# FRONT-UNIT-3_2-WIDE.net
KiCad netlist of a schematic drawn in Altium Designer
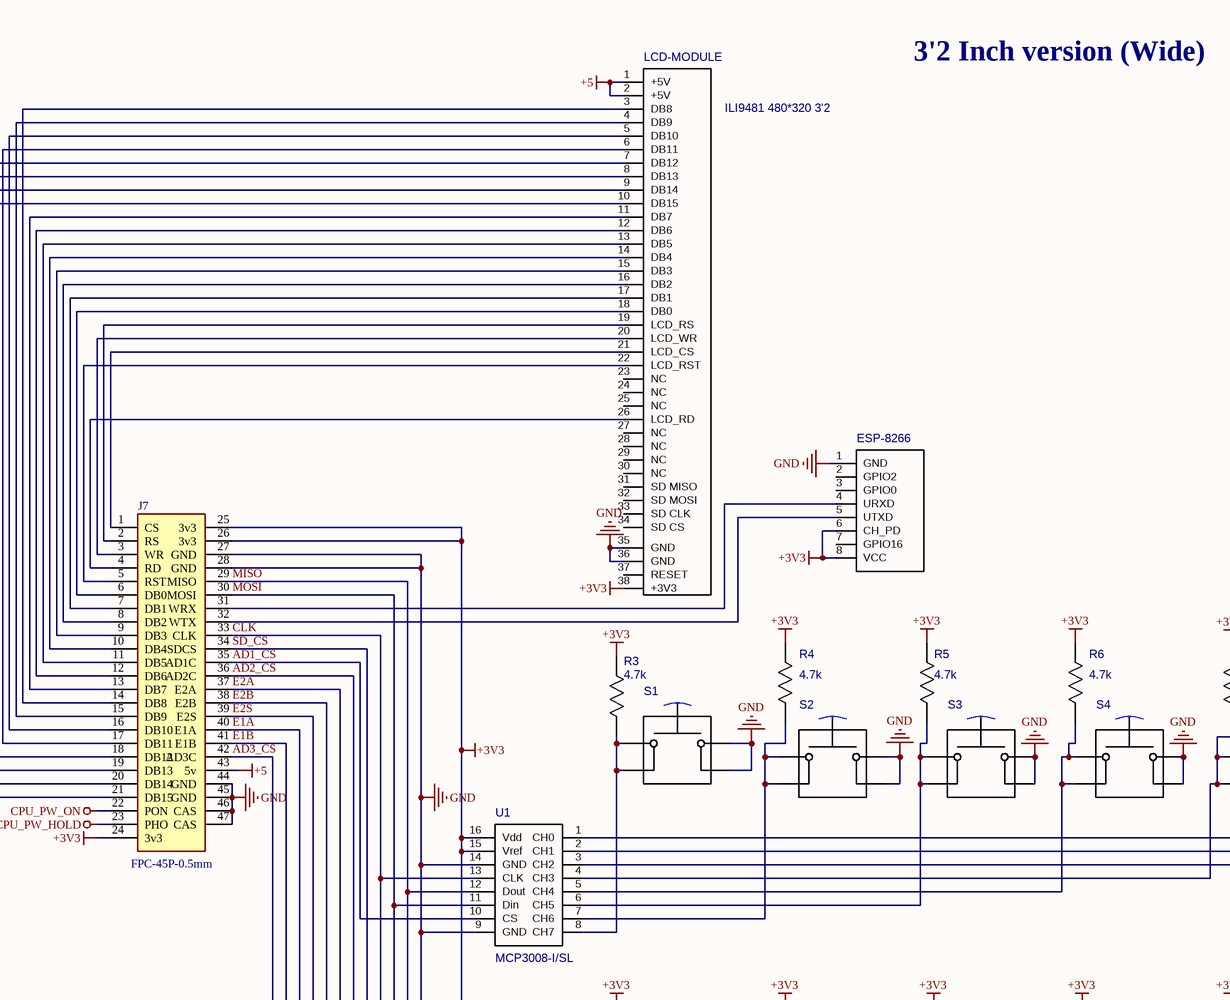
[diagram p0: FRONT-UNIT-3.2-WIDE.SCHDOC, top left]
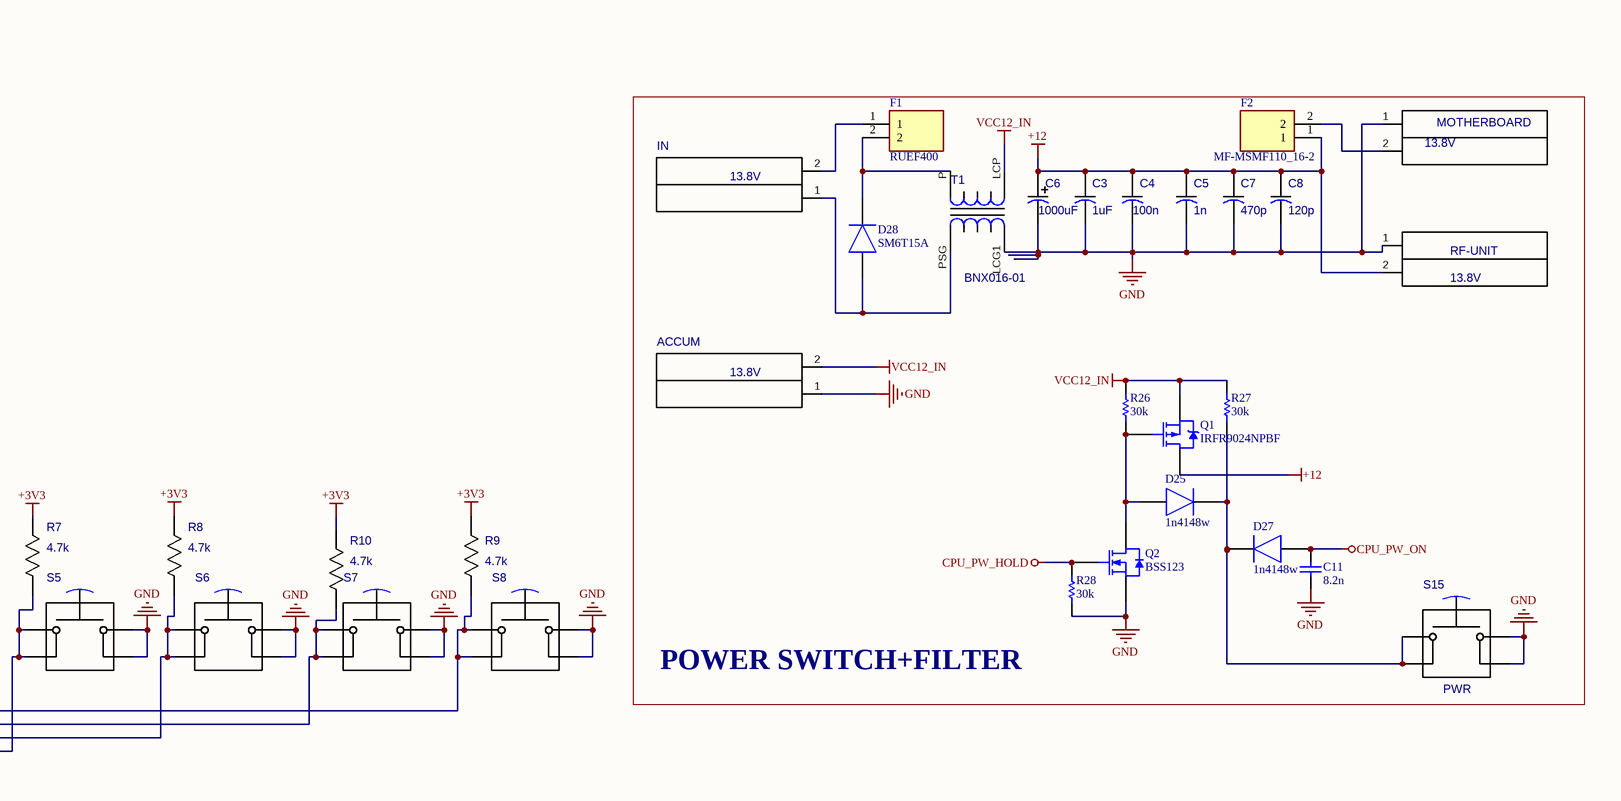
[diagram p1: FRONT-UNIT-3.2-WIDE.SCHDOC, top right]
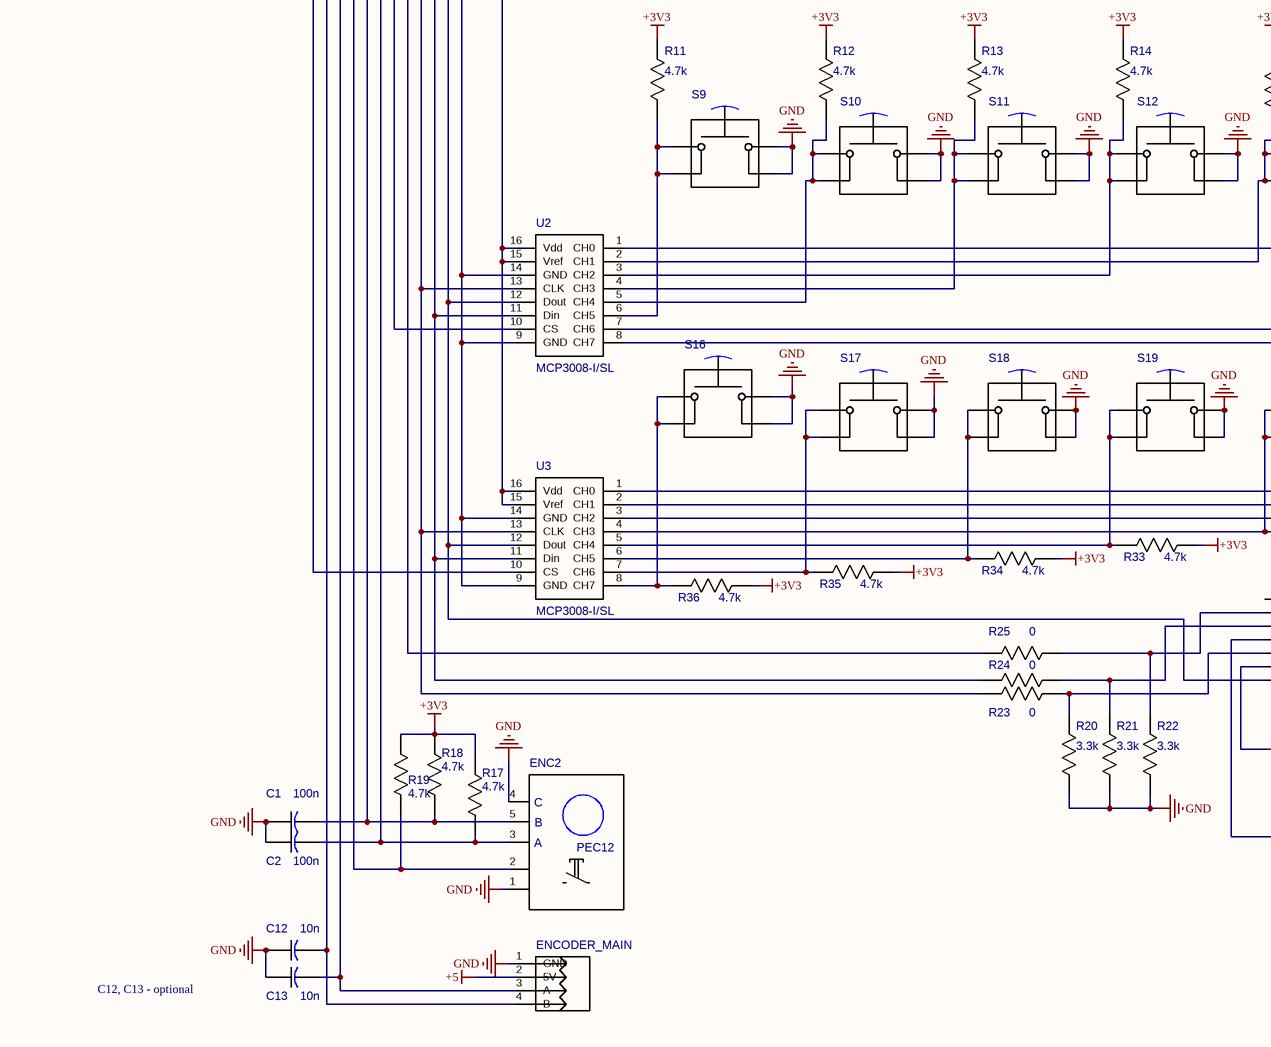
[diagram p2: FRONT-UNIT-3.2-WIDE.SCHDOC, bottom left]
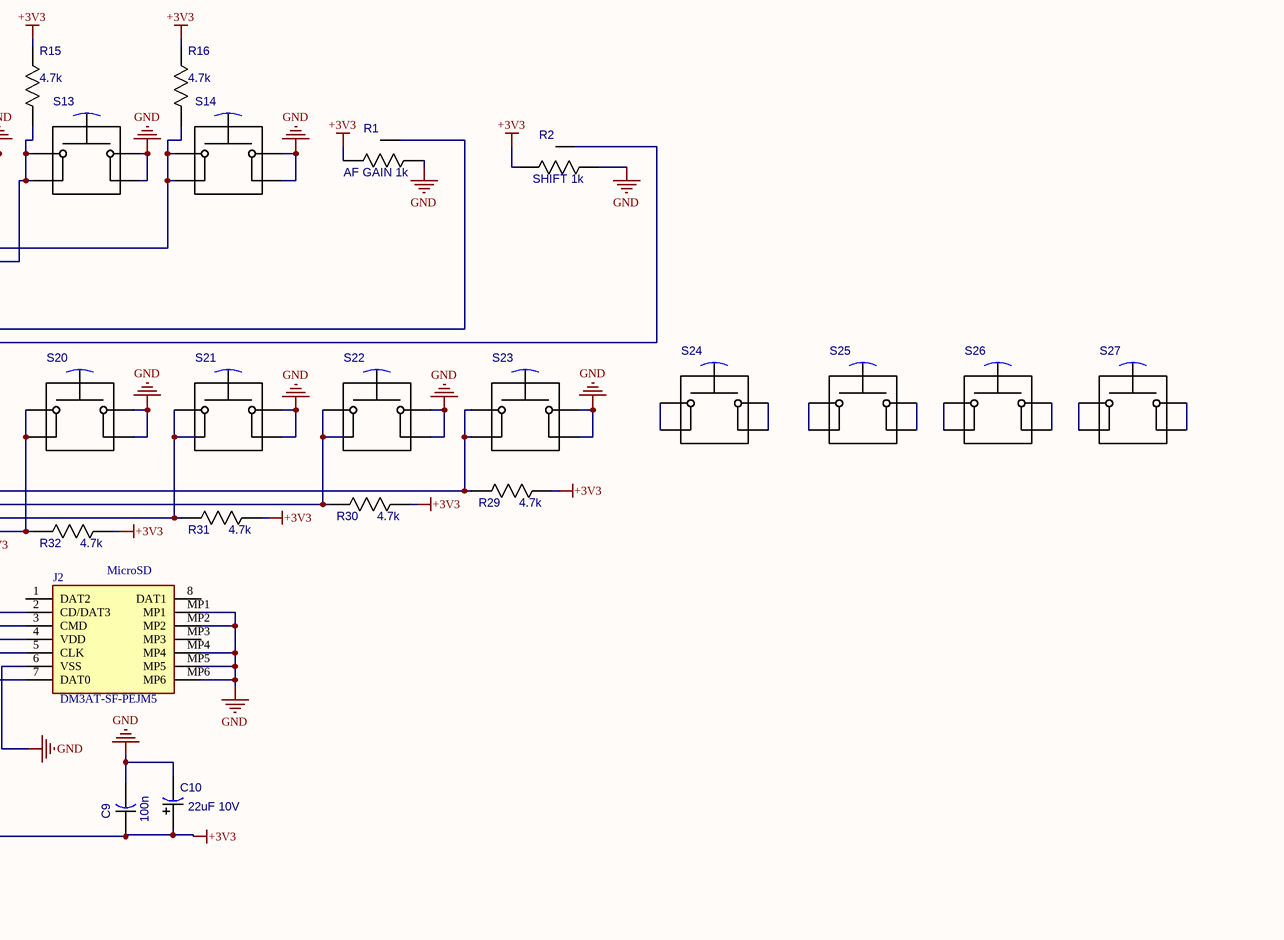
[diagram p3: FRONT-UNIT-3.2-WIDE.SCHDOC, bottom right]

(export (version "E")
  (design (tool "Eeschema 10.0.6"))
  (components
    (comp (ref "ACCUM")
      (value "13.8V")
      (footprint "JX2")
      (description "JX2")
      (libsource (lib "*") (part "JX2"))
    )
    (comp (ref "C1")
      (value "100n")
      (footprint "CAP_0805")
      (description "CAP_0805")
      (libsource (lib "*") (part "CAP_0805"))
    )
    (comp (ref "C2")
      (value "100n")
      (footprint "CAP_0805")
      (description "CAP_0805")
      (libsource (lib "*") (part "CAP_0805"))
    )
    (comp (ref "C3")
      (value "1uF")
      (footprint "CAP_1206")
      (description "CAP_1206")
      (libsource (lib "*") (part "CAP_1206"))
    )
    (comp (ref "C4")
      (value "100n")
      (footprint "CAP_1206")
      (description "CAP_1206")
      (libsource (lib "*") (part "CAP_1206"))
    )
    (comp (ref "C5")
      (value "1n")
      (footprint "CAP_1206")
      (description "CAP_1206")
      (libsource (lib "*") (part "CAP_1206"))
    )
    (comp (ref "C6")
      (value "1000uF")
      (footprint "CAP250RP")
      (description "CAP250RP")
      (libsource (lib "*") (part "CAP250RP"))
    )
    (comp (ref "C7")
      (value "470p")
      (footprint "CAP_1206")
      (description "CAP_1206")
      (libsource (lib "*") (part "CAP_1206"))
    )
    (comp (ref "C8")
      (value "120p")
      (footprint "CAP_1206")
      (description "CAP_1206")
      (libsource (lib "*") (part "CAP_1206"))
    )
    (comp (ref "C9")
      (value "100n")
      (footprint "CAP_0805")
      (description "CAP_0805")
      (libsource (lib "*") (part "CAP_0805"))
    )
    (comp (ref "C10")
      (value "22uF 10V")
      (footprint "EEEFC_sizeB")
      (description "EEEFC_sizeB")
      (libsource (lib "*") (part "EEEFC_sizeB"))
    )
    (comp (ref "C11")
      (value "8.2n")
      (footprint "CAPC2013X94X50LL20T25")
      (description "CAP_1206")
      (fields
        (field (name "MANUFACTURER") "AVX Interconnect / Elco")
        (field (name "PART NUMBER") "08055C822KAT2A")
      )
      (libsource (lib "Altium Content Vault") (part "CAP"))
    )
    (comp (ref "C12")
      (value "10n")
      (footprint "CAP_0805")
      (description "CAP_0805")
      (libsource (lib "*") (part "CAP_0805"))
    )
    (comp (ref "C13")
      (value "10n")
      (footprint "CAP_0805")
      (description "CAP_0805")
      (libsource (lib "*") (part "CAP_0805"))
    )
    (comp (ref "D25")
      (value "1n4148w")
      (footprint "SamacSys:SOD3716X135N")
      (description "Diode")
      (libsource (lib "*") (part "1n4148w"))
    )
    (comp (ref "D27")
      (value "1n4148w")
      (footprint "SamacSys:SOD3716X135N")
      (description "Diode")
      (libsource (lib "*") (part "1n4148w"))
    )
    (comp (ref "D28")
      (value "SM6T15A")
      (footprint "SamacSys:SMBJ36CATR")
      (description "Diode")
      (fields (field (name "MOUSER PART NUMBER") "511-SM6T15A") (field (name "RS PART NUMBER") "4864915P"))
      (libsource (lib "*") (part "SM6T15A"))
    )
    (comp (ref "ENC2") (value "PEC12") (footprint "PEC12") (libsource (lib "*") (part "PEC12")))
    (comp (ref "ENCODER_MAIN")
      (value "OPTICAL ENCODER")
      (footprint "644456-4")
      (libsource (lib "*") (part "644456-4"))
    )
    (comp (ref "ESP-8266")
      (value "ESP-01 ESP8266")
      (footprint "ESP-01 ESP8266")
      (libsource (lib "*") (part "ESP-01 ESP8266"))
    )
    (comp (ref "F1")
      (value "RUEF400")
      (footprint "SamacSys:RUEF400")
      (description "Fuse")
      (fields (field (name "MOUSER PART NUMBER") "650-RUEF400") (field (name "RS PART NUMBER") "5176837P"))
      (libsource (lib "*") (part "RUEF400"))
    )
    (comp (ref "F2")
      (value "MF-MSMF110_16-2")
      (footprint "SamacSys:FUSC4632X85N")
      (description "Fuse")
      (fields
        (field (name "MANUFACTURER_PART_NUMBER") "MF-MSMF110/16-2")
        (field (name "MOUSER PART NUMBER") "652-MF-MSMF110/16-2")
      )
      (libsource (lib "*") (part "MF-MSMF110_16-2"))
    )
    (comp (ref "IN") (value "13.8V") (footprint "JX2") (description "JX2") (libsource (lib "*") (part "JX2")))
    (comp (ref "J2")
      (value "DM3AT-SF-PEJM5")
      (footprint "SamacSys:DM3ATSFPEJM5")
      (description "Connector")
      (libsource (lib "*") (part "DM3AT-SF-PEJM5"))
    )
    (comp (ref "J7")
      (value "FPC-45P-0.5mm")
      (footprint "FRONT-UNIT-WIDE:FH12S45S05SH60")
      (description "Connector")
      (fields
        (field (name "MANUFACTURER_PART_NUMBER") "FH12S-45S-0.5SH(55)")
        (field (name "MOUSER PART NUMBER") "798-FH12S-45S-05SH55")
      )
      (libsource (lib "*") (part "FH12S-45S-0.5SH_55_"))
    )
    (comp (ref "LCD-MODULE")
      (value "ILI9481 480*320 3'2")
      (footprint "LCD-MODULE-3.2-480-320")
      (description "LCD-MODULE_3'2_480х320")
      (libsource (lib "FRONT-UNIT") (part "LCD-MODULE_3'2_480х320"))
    )
    (comp (ref "MOTHERBOARD")
      (value "13.8V")
      (footprint "JX2")
      (description "JX2")
      (libsource (lib "*") (part "JX2"))
    )
    (comp (ref "Q1")
      (value "IRFR9024NPBF")
      (footprint "ONSC-DPAK-3-369C-01_V")
      (description "IRFR9024NPBF, Транзистор, Р-канал 55В 11А")
      (fields (field (name "MANUFACTURER") "On Semiconductor") (field (name "PARTNUMBER") "NTD2955G"))
      (libsource (lib "Altium Content Vault") (part "ONSC-PMOS-G1S3D4-3_B"))
    )
    (comp (ref "Q2")
      (value "BSS123")
      (footprint "FAIR-SOT23-3_V")
      (fields (field (name "MANUFACTURER") "Fairchild"))
      (libsource (lib "Altium Content Vault") (part "NEMOS-GSD-3"))
    )
    (comp (ref "R1")
      (value "AF GAIN 1k")
      (footprint "PTV09")
      (description "Adjustable Resistor PTV09")
      (fields (field (name "Comment") "ptv09a-4225f-b102"))
      (libsource (lib "*") (part "PTV09"))
    )
    (comp (ref "R2")
      (value "SHIFT 1k")
      (footprint "PTV09")
      (description "Adjustable Resistor PTV09")
      (fields (field (name "Comment") "ptv09a-4225f-b102"))
      (libsource (lib "*") (part "PTV09"))
    )
    (comp (ref "R3")
      (value "4.7k")
      (footprint "RES_0805")
      (description "RES_0805")
      (libsource (lib "*") (part "RES_0805"))
    )
    (comp (ref "R4")
      (value "4.7k")
      (footprint "RES_0805")
      (description "RES_0805")
      (libsource (lib "*") (part "RES_0805"))
    )
    (comp (ref "R5")
      (value "4.7k")
      (footprint "RES_0805")
      (description "RES_0805")
      (libsource (lib "*") (part "RES_0805"))
    )
    (comp (ref "R6")
      (value "4.7k")
      (footprint "RES_0805")
      (description "RES_0805")
      (libsource (lib "*") (part "RES_0805"))
    )
    (comp (ref "R7")
      (value "4.7k")
      (footprint "RES_0805")
      (description "RES_0805")
      (libsource (lib "*") (part "RES_0805"))
    )
    (comp (ref "R8")
      (value "4.7k")
      (footprint "RES_0805")
      (description "RES_0805")
      (libsource (lib "*") (part "RES_0805"))
    )
    (comp (ref "R9")
      (value "4.7k")
      (footprint "RES_0805")
      (description "RES_0805")
      (libsource (lib "*") (part "RES_0805"))
    )
    (comp (ref "R10")
      (value "4.7k")
      (footprint "RES_0805")
      (description "RES_0805")
      (libsource (lib "*") (part "RES_0805"))
    )
    (comp (ref "R11")
      (value "4.7k")
      (footprint "RES_0805")
      (description "RES_0805")
      (libsource (lib "*") (part "RES_0805"))
    )
    (comp (ref "R12")
      (value "4.7k")
      (footprint "RES_0805")
      (description "RES_0805")
      (libsource (lib "*") (part "RES_0805"))
    )
    (comp (ref "R13")
      (value "4.7k")
      (footprint "RES_0805")
      (description "RES_0805")
      (libsource (lib "*") (part "RES_0805"))
    )
    (comp (ref "R14")
      (value "4.7k")
      (footprint "RES_0805")
      (description "RES_0805")
      (libsource (lib "*") (part "RES_0805"))
    )
    (comp (ref "R15")
      (value "4.7k")
      (footprint "RES_0805")
      (description "RES_0805")
      (libsource (lib "*") (part "RES_0805"))
    )
    (comp (ref "R16")
      (value "4.7k")
      (footprint "RES_0805")
      (description "RES_0805")
      (libsource (lib "*") (part "RES_0805"))
    )
    (comp (ref "R17")
      (value "4.7k")
      (footprint "RES_0805")
      (description "RES_0805")
      (libsource (lib "*") (part "RES_0805"))
    )
    (comp (ref "R18")
      (value "4.7k")
      (footprint "RES_0805")
      (description "RES_0805")
      (libsource (lib "*") (part "RES_0805"))
    )
    (comp (ref "R19")
      (value "4.7k")
      (footprint "RES_0805")
      (description "RES_0805")
      (libsource (lib "*") (part "RES_0805"))
    )
    (comp (ref "R20")
      (value "3.3k")
      (footprint "RES_0805")
      (description "RES_0805")
      (libsource (lib "*") (part "RES_0805"))
    )
    (comp (ref "R21")
      (value "3.3k")
      (footprint "RES_0805")
      (description "RES_0805")
      (libsource (lib "*") (part "RES_0805"))
    )
    (comp (ref "R22")
      (value "3.3k")
      (footprint "RES_0805")
      (description "RES_0805")
      (libsource (lib "*") (part "RES_0805"))
    )
    (comp (ref "R23")
      (value "0")
      (footprint "RES_0805")
      (description "RES_0805")
      (libsource (lib "*") (part "RES_0805"))
    )
    (comp (ref "R24")
      (value "0")
      (footprint "RES_0805")
      (description "RES_0805")
      (libsource (lib "*") (part "RES_0805"))
    )
    (comp (ref "R25")
      (value "0")
      (footprint "RES_0805")
      (description "RES_0805")
      (libsource (lib "*") (part "RES_0805"))
    )
    (comp (ref "R26")
      (value "30k")
      (footprint "RESC2013X60X40NL20T25")
      (description "RES_0805")
      (fields (field (name "MANUFACTURER") "Panasonic") (field (name "PART NUMBER") "ERA-6AEB303V"))
      (libsource (lib "Altium Content Vault") (part "RES"))
    )
    (comp (ref "R27")
      (value "30k")
      (footprint "RESC2013X60X40NL20T25")
      (description "RES_0805")
      (fields (field (name "MANUFACTURER") "Panasonic") (field (name "PART NUMBER") "ERA-6AEB303V"))
      (libsource (lib "Altium Content Vault") (part "RES"))
    )
    (comp (ref "R28")
      (value "30k")
      (footprint "RESC2013X60X40NL20T25")
      (description "RES_0805")
      (fields (field (name "MANUFACTURER") "Panasonic") (field (name "PART NUMBER") "ERA-6AEB303V"))
      (libsource (lib "Altium Content Vault") (part "RES"))
    )
    (comp (ref "R29")
      (value "4.7k")
      (footprint "RES_0805")
      (description "RES_0805")
      (libsource (lib "*") (part "RES_0805"))
    )
    (comp (ref "R30")
      (value "4.7k")
      (footprint "RES_0805")
      (description "RES_0805")
      (libsource (lib "*") (part "RES_0805"))
    )
    (comp (ref "R31")
      (value "4.7k")
      (footprint "RES_0805")
      (description "RES_0805")
      (libsource (lib "*") (part "RES_0805"))
    )
    (comp (ref "R32")
      (value "4.7k")
      (footprint "RES_0805")
      (description "RES_0805")
      (libsource (lib "*") (part "RES_0805"))
    )
    (comp (ref "R33")
      (value "4.7k")
      (footprint "RES_0805")
      (description "RES_0805")
      (libsource (lib "*") (part "RES_0805"))
    )
    (comp (ref "R34")
      (value "4.7k")
      (footprint "RES_0805")
      (description "RES_0805")
      (libsource (lib "*") (part "RES_0805"))
    )
    (comp (ref "R35")
      (value "4.7k")
      (footprint "RES_0805")
      (description "RES_0805")
      (libsource (lib "*") (part "RES_0805"))
    )
    (comp (ref "R36")
      (value "4.7k")
      (footprint "RES_0805")
      (description "RES_0805")
      (libsource (lib "*") (part "RES_0805"))
    )
    (comp (ref "RF-UNIT")
      (value "13.8V")
      (footprint "JX2")
      (description "JX2")
      (libsource (lib "*") (part "JX2"))
    )
    (comp (ref "S1")
      (value "PTS645SK50LFS")
      (footprint "PTS645SK50LFS")
      (fields (field (name "LCSC PART #") "test"))
      (libsource (lib "*") (part "PTS645SK50LFS"))
    )
    (comp (ref "S2")
      (value "PTS645SK50LFS")
      (footprint "PTS645SK50LFS")
      (libsource (lib "*") (part "PTS645SK50LFS"))
    )
    (comp (ref "S3")
      (value "PTS645SK50LFS")
      (footprint "PTS645SK50LFS")
      (libsource (lib "*") (part "PTS645SK50LFS"))
    )
    (comp (ref "S4")
      (value "PTS645SK50LFS")
      (footprint "PTS645SK50LFS")
      (libsource (lib "*") (part "PTS645SK50LFS"))
    )
    (comp (ref "S5")
      (value "PTS645SK50LFS")
      (footprint "PTS645SK50LFS")
      (libsource (lib "*") (part "PTS645SK50LFS"))
    )
    (comp (ref "S6")
      (value "PTS645SK50LFS")
      (footprint "PTS645SK50LFS")
      (libsource (lib "*") (part "PTS645SK50LFS"))
    )
    (comp (ref "S7")
      (value "PTS645SK50LFS")
      (footprint "PTS645SK50LFS")
      (libsource (lib "*") (part "PTS645SK50LFS"))
    )
    (comp (ref "S8")
      (value "PTS645SK50LFS")
      (footprint "PTS645SK50LFS")
      (libsource (lib "*") (part "PTS645SK50LFS"))
    )
    (comp (ref "S9")
      (value "PTS645SK50LFS")
      (footprint "PTS645SK50LFS")
      (libsource (lib "*") (part "PTS645SK50LFS"))
    )
    (comp (ref "S10")
      (value "PTS645SK50LFS")
      (footprint "PTS645SK50LFS")
      (libsource (lib "*") (part "PTS645SK50LFS"))
    )
    (comp (ref "S11")
      (value "PTS645SK50LFS")
      (footprint "PTS645SK50LFS")
      (libsource (lib "*") (part "PTS645SK50LFS"))
    )
    (comp (ref "S12")
      (value "PTS645SK50LFS")
      (footprint "PTS645SK50LFS")
      (libsource (lib "*") (part "PTS645SK50LFS"))
    )
    (comp (ref "S13")
      (value "PTS645SK50LFS")
      (footprint "PTS645SK50LFS")
      (libsource (lib "*") (part "PTS645SK50LFS"))
    )
    (comp (ref "S14")
      (value "PTS645SK50LFS")
      (footprint "PTS645SK50LFS")
      (libsource (lib "*") (part "PTS645SK50LFS"))
    )
    (comp (ref "S15")
      (value "PWR")
      (footprint "PTS645SK50LFS")
      (description "PTS645SK50LFS")
      (libsource (lib "*") (part "PTS645SK50LFS"))
    )
    (comp (ref "S16")
      (value "PTS645SK50LFS")
      (footprint "PTS645SK50LFS")
      (libsource (lib "*") (part "PTS645SK50LFS"))
    )
    (comp (ref "S17")
      (value "PTS645SK50LFS")
      (footprint "PTS645SK50LFS")
      (libsource (lib "*") (part "PTS645SK50LFS"))
    )
    (comp (ref "S18")
      (value "PTS645SK50LFS")
      (footprint "PTS645SK50LFS")
      (libsource (lib "*") (part "PTS645SK50LFS"))
    )
    (comp (ref "S19")
      (value "PTS645SK50LFS")
      (footprint "PTS645SK50LFS")
      (libsource (lib "*") (part "PTS645SK50LFS"))
    )
    (comp (ref "S20")
      (value "PTS645SK50LFS")
      (footprint "PTS645SK50LFS")
      (libsource (lib "*") (part "PTS645SK50LFS"))
    )
    (comp (ref "S21")
      (value "PTS645SK50LFS")
      (footprint "PTS645SK50LFS")
      (libsource (lib "*") (part "PTS645SK50LFS"))
    )
    (comp (ref "S22")
      (value "PTS645SK50LFS")
      (footprint "PTS645SK50LFS")
      (libsource (lib "*") (part "PTS645SK50LFS"))
    )
    (comp (ref "S23")
      (value "PTS645SK50LFS")
      (footprint "PTS645SK50LFS")
      (libsource (lib "*") (part "PTS645SK50LFS"))
    )
    (comp (ref "S24")
      (value "PTS645SK50LFS")
      (footprint "PTS645SK50LFS")
      (libsource (lib "*") (part "PTS645SK50LFS"))
    )
    (comp (ref "S25")
      (value "PTS645SK50LFS")
      (footprint "PTS645SK50LFS")
      (libsource (lib "*") (part "PTS645SK50LFS"))
    )
    (comp (ref "S26")
      (value "PTS645SK50LFS")
      (footprint "PTS645SK50LFS")
      (libsource (lib "*") (part "PTS645SK50LFS"))
    )
    (comp (ref "S27")
      (value "PTS645SK50LFS")
      (footprint "PTS645SK50LFS")
      (libsource (lib "*") (part "PTS645SK50LFS"))
    )
    (comp (ref "T1")
      (value "BNX016-01")
      (footprint "TRANSF_ICORE")
      (libsource (lib "*") (part "TRANSF_ICORE"))
    )
    (comp (ref "U1")
      (value "MCP3008-I/SL")
      (footprint "MCP3008-I/SL")
      (libsource (lib "*") (part "MCP3008-I/SL"))
    )
    (comp (ref "U2")
      (value "MCP3008-I/SL")
      (footprint "MCP3008-I/SL")
      (libsource (lib "*") (part "MCP3008-I/SL"))
    )
    (comp (ref "U3")
      (value "MCP3008-I/SL")
      (footprint "MCP3008-I/SL")
      (libsource (lib "*") (part "MCP3008-I/SL"))
    )
  )
  (nets
    (net (code "1") (name "+3V3") (class "Default")
      (node (ref "C10") (pin "1") (pinfunction "PLUS_1") (pintype "passive"))
      (node (ref "C9") (pin "1") (pinfunction "1_1") (pintype "passive"))
      (node (ref "ESP-8266") (pin "6") (pinfunction "CH_PD_6") (pintype "passive"))
      (node (ref "ESP-8266") (pin "8") (pinfunction "VCC_8") (pintype "passive"))
      (node (ref "J2") (pin "4") (pinfunction "VDD_4") (pintype "passive"))
      (node (ref "J7") (pin "24") (pinfunction "3v3_24") (pintype "passive"))
      (node (ref "J7") (pin "25") (pinfunction "3v3_25") (pintype "passive"))
      (node (ref "J7") (pin "26") (pinfunction "3v3_26") (pintype "passive"))
      (node (ref "LCD-MODULE") (pin "38") (pinfunction "+3V3_38") (pintype "passive"))
      (node (ref "R1") (pin "1") (pinfunction "CW_1") (pintype "passive"))
      (node (ref "R10") (pin "2") (pinfunction "2_2") (pintype "passive"))
      (node (ref "R11") (pin "2") (pinfunction "2_2") (pintype "passive"))
      (node (ref "R12") (pin "2") (pinfunction "2_2") (pintype "passive"))
      (node (ref "R13") (pin "2") (pinfunction "2_2") (pintype "passive"))
      (node (ref "R14") (pin "2") (pinfunction "2_2") (pintype "passive"))
      (node (ref "R15") (pin "2") (pinfunction "2_2") (pintype "passive"))
      (node (ref "R16") (pin "2") (pinfunction "2_2") (pintype "passive"))
      (node (ref "R17") (pin "2") (pinfunction "2_2") (pintype "passive"))
      (node (ref "R18") (pin "2") (pinfunction "2_2") (pintype "passive"))
      (node (ref "R19") (pin "2") (pinfunction "2_2") (pintype "passive"))
      (node (ref "R2") (pin "1") (pinfunction "CW_1") (pintype "passive"))
      (node (ref "R29") (pin "2") (pinfunction "2_2") (pintype "passive"))
      (node (ref "R3") (pin "2") (pinfunction "2_2") (pintype "passive"))
      (node (ref "R30") (pin "2") (pinfunction "2_2") (pintype "passive"))
      (node (ref "R31") (pin "2") (pinfunction "2_2") (pintype "passive"))
      (node (ref "R32") (pin "2") (pinfunction "2_2") (pintype "passive"))
      (node (ref "R33") (pin "2") (pinfunction "2_2") (pintype "passive"))
      (node (ref "R34") (pin "2") (pinfunction "2_2") (pintype "passive"))
      (node (ref "R35") (pin "2") (pinfunction "2_2") (pintype "passive"))
      (node (ref "R36") (pin "2") (pinfunction "2_2") (pintype "passive"))
      (node (ref "R4") (pin "2") (pinfunction "2_2") (pintype "passive"))
      (node (ref "R5") (pin "2") (pinfunction "2_2") (pintype "passive"))
      (node (ref "R6") (pin "2") (pinfunction "2_2") (pintype "passive"))
      (node (ref "R7") (pin "2") (pinfunction "2_2") (pintype "passive"))
      (node (ref "R8") (pin "2") (pinfunction "2_2") (pintype "passive"))
      (node (ref "R9") (pin "2") (pinfunction "2_2") (pintype "passive"))
      (node (ref "U1") (pin "15") (pinfunction "Vref_15") (pintype "passive"))
      (node (ref "U1") (pin "16") (pinfunction "Vdd_16") (pintype "passive"))
      (node (ref "U2") (pin "15") (pinfunction "Vref_15") (pintype "passive"))
      (node (ref "U2") (pin "16") (pinfunction "Vdd_16") (pintype "passive"))
      (node (ref "U3") (pin "15") (pinfunction "Vref_15") (pintype "passive"))
      (node (ref "U3") (pin "16") (pinfunction "Vdd_16") (pintype "passive"))
    )
    (net (code "2") (name "+5") (class "Default")
      (node (ref "ENCODER_MAIN") (pin "2") (pinfunction "5V_2") (pintype "passive"))
      (node (ref "J7") (pin "43") (pinfunction "5v_43") (pintype "passive"))
      (node (ref "LCD-MODULE") (pin "1") (pinfunction "+5V_1") (pintype "passive"))
      (node (ref "LCD-MODULE") (pin "2") (pinfunction "+5V_2") (pintype "passive"))
    )
    (net (code "3") (name "+12") (class "Default")
      (node (ref "C3") (pin "1") (pinfunction "1_1") (pintype "passive"))
      (node (ref "C4") (pin "1") (pinfunction "1_1") (pintype "passive"))
      (node (ref "C5") (pin "1") (pinfunction "1_1") (pintype "passive"))
      (node (ref "C6") (pin "1") (pinfunction "PLUS_1") (pintype "passive"))
      (node (ref "C7") (pin "1") (pinfunction "1_1") (pintype "passive"))
      (node (ref "C8") (pin "1") (pinfunction "1_1") (pintype "passive"))
      (node (ref "F2") (pin "1") (pinfunction "1_1") (pintype "passive"))
      (node (ref "Q1") (pin "4") (pinfunction "D_4") (pintype "passive"))
      (node (ref "RF-UNIT") (pin "2") (pinfunction "2_2") (pintype "passive"))
    )
    (net (code "4") (name "/AD1_CS") (class "Default")
      (node (ref "J7") (pin "35") (pinfunction "AD1C_35") (pintype "passive"))
      (node (ref "U1") (pin "10") (pinfunction "CS_10") (pintype "passive"))
    )
    (net (code "5") (name "/AD2_CS") (class "Default")
      (node (ref "J7") (pin "36") (pinfunction "AD2C_36") (pintype "passive"))
      (node (ref "U2") (pin "10") (pinfunction "CS_10") (pintype "passive"))
    )
    (net (code "6") (name "/AD3_CS") (class "Default")
      (node (ref "J7") (pin "42") (pinfunction "AD3C_42") (pintype "passive"))
      (node (ref "U3") (pin "10") (pinfunction "CS_10") (pintype "passive"))
    )
    (net (code "7") (name "/CLK") (class "Default")
      (node (ref "J7") (pin "33") (pinfunction "CLK_33") (pintype "passive"))
      (node (ref "R23") (pin "2") (pinfunction "2_2") (pintype "passive"))
      (node (ref "U1") (pin "13") (pinfunction "CLK_13") (pintype "passive"))
      (node (ref "U2") (pin "13") (pinfunction "CLK_13") (pintype "passive"))
      (node (ref "U3") (pin "13") (pinfunction "CLK_13") (pintype "passive"))
    )
    (net (code "8") (name "/E1A") (class "Default")
      (node (ref "C13") (pin "2") (pinfunction "2_2") (pintype "passive"))
      (node (ref "ENCODER_MAIN") (pin "3") (pinfunction "A_3") (pintype "passive"))
      (node (ref "J7") (pin "40") (pinfunction "E1A_40") (pintype "passive"))
    )
    (net (code "9") (name "/E1B") (class "Default")
      (node (ref "C12") (pin "2") (pinfunction "2_2") (pintype "passive"))
      (node (ref "ENCODER_MAIN") (pin "4") (pinfunction "B_4") (pintype "passive"))
      (node (ref "J7") (pin "41") (pinfunction "E1B_41") (pintype "passive"))
    )
    (net (code "10") (name "/E2A") (class "Default")
      (node (ref "C2") (pin "2") (pinfunction "2_2") (pintype "passive"))
      (node (ref "ENC2") (pin "3") (pinfunction "A_3") (pintype "passive"))
      (node (ref "J7") (pin "37") (pinfunction "E2A_37") (pintype "passive"))
      (node (ref "R17") (pin "1") (pinfunction "1_1") (pintype "passive"))
    )
    (net (code "11") (name "/E2B") (class "Default")
      (node (ref "C1") (pin "2") (pinfunction "2_2") (pintype "passive"))
      (node (ref "ENC2") (pin "5") (pinfunction "B_5") (pintype "passive"))
      (node (ref "J7") (pin "38") (pinfunction "E2B_38") (pintype "passive"))
      (node (ref "R18") (pin "1") (pinfunction "1_1") (pintype "passive"))
    )
    (net (code "12") (name "/E2S") (class "Default")
      (node (ref "ENC2") (pin "2") (pinfunction "2_2") (pintype "passive"))
      (node (ref "J7") (pin "39") (pinfunction "E2S_39") (pintype "passive"))
      (node (ref "R19") (pin "1") (pinfunction "1_1") (pintype "passive"))
    )
    (net (code "13") (name "/MISO") (class "Default")
      (node (ref "J2") (pin "7") (pinfunction "DAT0_7") (pintype "passive"))
      (node (ref "J7") (pin "29") (pinfunction "MISO_29") (pintype "passive"))
      (node (ref "U1") (pin "12") (pinfunction "Dout_12") (pintype "passive"))
      (node (ref "U2") (pin "12") (pinfunction "Dout_12") (pintype "passive"))
      (node (ref "U3") (pin "12") (pinfunction "Dout_12") (pintype "passive"))
    )
    (net (code "14") (name "/MOSI") (class "Default")
      (node (ref "J7") (pin "30") (pinfunction "MOSI_30") (pintype "passive"))
      (node (ref "R24") (pin "2") (pinfunction "2_2") (pintype "passive"))
      (node (ref "U1") (pin "11") (pinfunction "Din_11") (pintype "passive"))
      (node (ref "U2") (pin "11") (pinfunction "Din_11") (pintype "passive"))
      (node (ref "U3") (pin "11") (pinfunction "Din_11") (pintype "passive"))
    )
    (net (code "15") (name "/SD_CS") (class "Default")
      (node (ref "J7") (pin "34") (pinfunction "SDCS_34") (pintype "passive"))
      (node (ref "R25") (pin "2") (pinfunction "2_2") (pintype "passive"))
    )
    (net (code "16") (name "CPU_PW_HOLD") (class "Default")
      (node (ref "J7") (pin "23") (pinfunction "PHO_23") (pintype "passive"))
      (node (ref "Q2") (pin "1") (pinfunction "G_1") (pintype "passive"))
      (node (ref "R28") (pin "2") (pinfunction "2_2") (pintype "passive"))
    )
    (net (code "17") (name "CPU_PW_ON") (class "Default")
      (node (ref "C11") (pin "2") (pinfunction "2_2") (pintype "passive"))
      (node (ref "D27") (pin "2") (pinfunction "A_2") (pintype "passive"))
      (node (ref "J7") (pin "22") (pinfunction "PON_22") (pintype "passive"))
    )
    (net (code "18") (name "GND") (class "Default")
      (node (ref "ACCUM") (pin "1") (pinfunction "1_1") (pintype "passive"))
      (node (ref "C1") (pin "1") (pinfunction "1_1") (pintype "passive"))
      (node (ref "C10") (pin "2") (pinfunction "MINUS_2") (pintype "passive"))
      (node (ref "C11") (pin "1") (pinfunction "1_1") (pintype "passive"))
      (node (ref "C12") (pin "1") (pinfunction "1_1") (pintype "passive"))
      (node (ref "C13") (pin "1") (pinfunction "1_1") (pintype "passive"))
      (node (ref "C2") (pin "1") (pinfunction "1_1") (pintype "passive"))
      (node (ref "C3") (pin "2") (pinfunction "2_2") (pintype "passive"))
      (node (ref "C4") (pin "2") (pinfunction "2_2") (pintype "passive"))
      (node (ref "C5") (pin "2") (pinfunction "2_2") (pintype "passive"))
      (node (ref "C6") (pin "2") (pinfunction "MINUS_2") (pintype "passive"))
      (node (ref "C7") (pin "2") (pinfunction "2_2") (pintype "passive"))
      (node (ref "C8") (pin "2") (pinfunction "2_2") (pintype "passive"))
      (node (ref "C9") (pin "2") (pinfunction "2_2") (pintype "passive"))
      (node (ref "ENC2") (pin "1") (pinfunction "1_1") (pintype "passive"))
      (node (ref "ENC2") (pin "4") (pinfunction "C_4") (pintype "passive"))
      (node (ref "ENCODER_MAIN") (pin "1") (pinfunction "GND_1") (pintype "passive"))
      (node (ref "ESP-8266") (pin "1") (pinfunction "GND_1") (pintype "passive"))
      (node (ref "J2") (pin "6") (pinfunction "VSS_6") (pintype "passive"))
      (node (ref "J2") (pin "MP1") (pinfunction "MP1_MP1") (pintype "passive"))
      (node (ref "J2") (pin "MP2") (pinfunction "MP2_MP2") (pintype "passive"))
      (node (ref "J2") (pin "MP4") (pinfunction "MP4_MP4") (pintype "passive"))
      (node (ref "J2") (pin "MP5") (pinfunction "MP5_MP5") (pintype "passive"))
      (node (ref "J2") (pin "MP6") (pinfunction "MP6_MP6") (pintype "passive"))
      (node (ref "J7") (pin "27") (pinfunction "GND_27") (pintype "passive"))
      (node (ref "J7") (pin "28") (pinfunction "GND_28") (pintype "passive"))
      (node (ref "J7") (pin "44") (pinfunction "GND_44") (pintype "passive"))
      (node (ref "J7") (pin "45") (pinfunction "GND_45") (pintype "passive"))
      (node (ref "J7") (pin "46") (pinfunction "CAS_46") (pintype "passive"))
      (node (ref "J7") (pin "47") (pinfunction "CAS_47") (pintype "passive"))
      (node (ref "LCD-MODULE") (pin "35") (pinfunction "GND_35") (pintype "passive"))
      (node (ref "LCD-MODULE") (pin "36") (pinfunction "GND_36") (pintype "passive"))
      (node (ref "MOTHERBOARD") (pin "1") (pinfunction "1_1") (pintype "passive"))
      (node (ref "Q2") (pin "2") (pinfunction "S_2") (pintype "passive"))
      (node (ref "R1") (pin "3") (pinfunction "CCW_3") (pintype "passive"))
      (node (ref "R2") (pin "3") (pinfunction "CCW_3") (pintype "passive"))
      (node (ref "R20") (pin "1") (pinfunction "1_1") (pintype "passive"))
      (node (ref "R21") (pin "1") (pinfunction "1_1") (pintype "passive"))
      (node (ref "R22") (pin "1") (pinfunction "1_1") (pintype "passive"))
      (node (ref "R28") (pin "1") (pinfunction "1_1") (pintype "passive"))
      (node (ref "RF-UNIT") (pin "1") (pinfunction "1_1") (pintype "passive"))
      (node (ref "S1") (pin "3") (pinfunction "B_3") (pintype "passive"))
      (node (ref "S1") (pin "4") (pinfunction "B_4") (pintype "passive"))
      (node (ref "S10") (pin "3") (pinfunction "B_3") (pintype "passive"))
      (node (ref "S10") (pin "4") (pinfunction "B_4") (pintype "passive"))
      (node (ref "S11") (pin "3") (pinfunction "B_3") (pintype "passive"))
      (node (ref "S11") (pin "4") (pinfunction "B_4") (pintype "passive"))
      (node (ref "S12") (pin "3") (pinfunction "B_3") (pintype "passive"))
      (node (ref "S12") (pin "4") (pinfunction "B_4") (pintype "passive"))
      (node (ref "S13") (pin "3") (pinfunction "B_3") (pintype "passive"))
      (node (ref "S13") (pin "4") (pinfunction "B_4") (pintype "passive"))
      (node (ref "S14") (pin "3") (pinfunction "B_3") (pintype "passive"))
      (node (ref "S14") (pin "4") (pinfunction "B_4") (pintype "passive"))
      (node (ref "S15") (pin "3") (pinfunction "B_3") (pintype "passive"))
      (node (ref "S15") (pin "4") (pinfunction "B_4") (pintype "passive"))
      (node (ref "S16") (pin "3") (pinfunction "B_3") (pintype "passive"))
      (node (ref "S16") (pin "4") (pinfunction "B_4") (pintype "passive"))
      (node (ref "S17") (pin "3") (pinfunction "B_3") (pintype "passive"))
      (node (ref "S17") (pin "4") (pinfunction "B_4") (pintype "passive"))
      (node (ref "S18") (pin "3") (pinfunction "B_3") (pintype "passive"))
      (node (ref "S18") (pin "4") (pinfunction "B_4") (pintype "passive"))
      (node (ref "S19") (pin "3") (pinfunction "B_3") (pintype "passive"))
      (node (ref "S19") (pin "4") (pinfunction "B_4") (pintype "passive"))
      (node (ref "S2") (pin "3") (pinfunction "B_3") (pintype "passive"))
      (node (ref "S2") (pin "4") (pinfunction "B_4") (pintype "passive"))
      (node (ref "S20") (pin "3") (pinfunction "B_3") (pintype "passive"))
      (node (ref "S20") (pin "4") (pinfunction "B_4") (pintype "passive"))
      (node (ref "S21") (pin "3") (pinfunction "B_3") (pintype "passive"))
      (node (ref "S21") (pin "4") (pinfunction "B_4") (pintype "passive"))
      (node (ref "S22") (pin "3") (pinfunction "B_3") (pintype "passive"))
      (node (ref "S22") (pin "4") (pinfunction "B_4") (pintype "passive"))
      (node (ref "S23") (pin "3") (pinfunction "B_3") (pintype "passive"))
      (node (ref "S23") (pin "4") (pinfunction "B_4") (pintype "passive"))
      (node (ref "S3") (pin "3") (pinfunction "B_3") (pintype "passive"))
      (node (ref "S3") (pin "4") (pinfunction "B_4") (pintype "passive"))
      (node (ref "S4") (pin "3") (pinfunction "B_3") (pintype "passive"))
      (node (ref "S4") (pin "4") (pinfunction "B_4") (pintype "passive"))
      (node (ref "S5") (pin "3") (pinfunction "B_3") (pintype "passive"))
      (node (ref "S5") (pin "4") (pinfunction "B_4") (pintype "passive"))
      (node (ref "S6") (pin "3") (pinfunction "B_3") (pintype "passive"))
      (node (ref "S6") (pin "4") (pinfunction "B_4") (pintype "passive"))
      (node (ref "S7") (pin "3") (pinfunction "B_3") (pintype "passive"))
      (node (ref "S7") (pin "4") (pinfunction "B_4") (pintype "passive"))
      (node (ref "S8") (pin "3") (pinfunction "B_3") (pintype "passive"))
      (node (ref "S8") (pin "4") (pinfunction "B_4") (pintype "passive"))
      (node (ref "S9") (pin "3") (pinfunction "B_3") (pintype "passive"))
      (node (ref "S9") (pin "4") (pinfunction "B_4") (pintype "passive"))
      (node (ref "T1") (pin "LCG1") (pinfunction "S2_LCG1") (pintype "passive"))
      (node (ref "T1") (pin "LCG2") (pinfunction "0_LCG2") (pintype "passive"))
      (node (ref "T1") (pin "LCG3") (pinfunction "0_LCG3") (pintype "passive"))
      (node (ref "U1") (pin "14") (pinfunction "GND_14") (pintype "passive"))
      (node (ref "U1") (pin "9") (pinfunction "GND_9") (pintype "passive"))
      (node (ref "U2") (pin "14") (pinfunction "GND_14") (pintype "passive"))
      (node (ref "U2") (pin "9") (pinfunction "GND_9") (pintype "passive"))
      (node (ref "U3") (pin "14") (pinfunction "GND_14") (pintype "passive"))
      (node (ref "U3") (pin "9") (pinfunction "GND_9") (pintype "passive"))
    )
    (net (code "19") (name "Net-(D25-A)") (class "Default")
      (node (ref "D25") (pin "2") (pinfunction "A_2") (pintype "passive"))
      (node (ref "Q1") (pin "1") (pinfunction "G_1") (pintype "passive"))
      (node (ref "Q2") (pin "3") (pinfunction "D_3") (pintype "passive"))
      (node (ref "R26") (pin "1") (pinfunction "1_1") (pintype "passive"))
    )
    (net (code "20") (name "Net-(D25-K)") (class "Default")
      (node (ref "D25") (pin "1") (pinfunction "K_1") (pintype "passive"))
      (node (ref "D27") (pin "1") (pinfunction "K_1") (pintype "passive"))
      (node (ref "R27") (pin "1") (pinfunction "1_1") (pintype "passive"))
      (node (ref "S15") (pin "1") (pinfunction "A_1") (pintype "passive"))
      (node (ref "S15") (pin "2") (pinfunction "A_2") (pintype "passive"))
    )
    (net (code "21") (name "Net-(D28-A)") (class "Default")
      (node (ref "D28") (pin "2") (pinfunction "A_2") (pintype "passive"))
      (node (ref "IN") (pin "1") (pinfunction "1_1") (pintype "passive"))
      (node (ref "T1") (pin "PSG") (pinfunction "S1_PSG") (pintype "passive"))
    )
    (net (code "22") (name "Net-(D28-K)") (class "Default")
      (node (ref "D28") (pin "1") (pinfunction "K_1") (pintype "passive"))
      (node (ref "F1") (pin "2") (pinfunction "2_2") (pintype "passive"))
      (node (ref "T1") (pin "P") (pinfunction "P1_P") (pintype "passive"))
    )
    (net (code "23") (name "Net-(ESP-8266-URXD)") (class "Default")
      (node (ref "ESP-8266") (pin "4") (pinfunction "URXD_4") (pintype "passive"))
      (node (ref "J7") (pin "31") (pinfunction "WRX_31") (pintype "passive"))
    )
    (net (code "24") (name "Net-(ESP-8266-UTXD)") (class "Default")
      (node (ref "ESP-8266") (pin "5") (pinfunction "UTXD_5") (pintype "passive"))
      (node (ref "J7") (pin "32") (pinfunction "WTX_32") (pintype "passive"))
    )
    (net (code "25") (name "Net-(F1-Pad1)") (class "Default")
      (node (ref "F1") (pin "1") (pinfunction "1_1") (pintype "passive"))
      (node (ref "IN") (pin "2") (pinfunction "2_2") (pintype "passive"))
    )
    (net (code "26") (name "Net-(F2-Pad2)") (class "Default")
      (node (ref "F2") (pin "2") (pinfunction "2_2") (pintype "passive"))
      (node (ref "MOTHERBOARD") (pin "2") (pinfunction "2_2") (pintype "passive"))
    )
    (net (code "27") (name "Net-(J2-CD{slash}DAT3)") (class "Default")
      (node (ref "J2") (pin "2") (pinfunction "CD/DAT3_2") (pintype "passive"))
      (node (ref "R22") (pin "2") (pinfunction "2_2") (pintype "passive"))
      (node (ref "R25") (pin "1") (pinfunction "1_1") (pintype "passive"))
    )
    (net (code "28") (name "Net-(J2-CLK)") (class "Default")
      (node (ref "J2") (pin "5") (pinfunction "CLK_5") (pintype "passive"))
      (node (ref "R20") (pin "2") (pinfunction "2_2") (pintype "passive"))
      (node (ref "R23") (pin "1") (pinfunction "1_1") (pintype "passive"))
    )
    (net (code "29") (name "Net-(J2-CMD)") (class "Default")
      (node (ref "J2") (pin "3") (pinfunction "CMD_3") (pintype "passive"))
      (node (ref "R21") (pin "2") (pinfunction "2_2") (pintype "passive"))
      (node (ref "R24") (pin "1") (pinfunction "1_1") (pintype "passive"))
    )
    (net (code "30") (name "Net-(J7-CS)") (class "Default")
      (node (ref "J7") (pin "1") (pinfunction "CS_1") (pintype "passive"))
      (node (ref "LCD-MODULE") (pin "21") (pinfunction "LCD_CS_21") (pintype "passive"))
    )
    (net (code "31") (name "Net-(J7-DB0)") (class "Default")
      (node (ref "J7") (pin "6") (pinfunction "DB0_6") (pintype "passive"))
      (node (ref "LCD-MODULE") (pin "18") (pinfunction "DB0_18") (pintype "passive"))
    )
    (net (code "32") (name "Net-(J7-DB1)") (class "Default")
      (node (ref "J7") (pin "7") (pinfunction "DB1_7") (pintype "passive"))
      (node (ref "LCD-MODULE") (pin "17") (pinfunction "DB1_17") (pintype "passive"))
    )
    (net (code "33") (name "Net-(J7-DB2)") (class "Default")
      (node (ref "J7") (pin "8") (pinfunction "DB2_8") (pintype "passive"))
      (node (ref "LCD-MODULE") (pin "16") (pinfunction "DB2_16") (pintype "passive"))
    )
    (net (code "34") (name "Net-(J7-DB3)") (class "Default")
      (node (ref "J7") (pin "9") (pinfunction "DB3_9") (pintype "passive"))
      (node (ref "LCD-MODULE") (pin "15") (pinfunction "DB3_15") (pintype "passive"))
    )
    (net (code "35") (name "Net-(J7-DB4)") (class "Default")
      (node (ref "J7") (pin "10") (pinfunction "DB4_10") (pintype "passive"))
      (node (ref "LCD-MODULE") (pin "14") (pinfunction "DB4_14") (pintype "passive"))
    )
    (net (code "36") (name "Net-(J7-DB5)") (class "Default")
      (node (ref "J7") (pin "11") (pinfunction "DB5_11") (pintype "passive"))
      (node (ref "LCD-MODULE") (pin "13") (pinfunction "DB5_13") (pintype "passive"))
    )
    (net (code "37") (name "Net-(J7-DB6)") (class "Default")
      (node (ref "J7") (pin "12") (pinfunction "DB6_12") (pintype "passive"))
      (node (ref "LCD-MODULE") (pin "12") (pinfunction "DB6_12") (pintype "passive"))
    )
    (net (code "38") (name "Net-(J7-DB7)") (class "Default")
      (node (ref "J7") (pin "13") (pinfunction "DB7_13") (pintype "passive"))
      (node (ref "LCD-MODULE") (pin "11") (pinfunction "DB7_11") (pintype "passive"))
    )
    (net (code "39") (name "Net-(J7-DB8)") (class "Default")
      (node (ref "J7") (pin "14") (pinfunction "DB8_14") (pintype "passive"))
      (node (ref "LCD-MODULE") (pin "3") (pinfunction "DB8_3") (pintype "passive"))
    )
    (net (code "40") (name "Net-(J7-DB9)") (class "Default")
      (node (ref "J7") (pin "15") (pinfunction "DB9_15") (pintype "passive"))
      (node (ref "LCD-MODULE") (pin "4") (pinfunction "DB9_4") (pintype "passive"))
    )
    (net (code "41") (name "Net-(J7-DB10)") (class "Default")
      (node (ref "J7") (pin "16") (pinfunction "DB10_16") (pintype "passive"))
      (node (ref "LCD-MODULE") (pin "5") (pinfunction "DB10_5") (pintype "passive"))
    )
    (net (code "42") (name "Net-(J7-DB11)") (class "Default")
      (node (ref "J7") (pin "17") (pinfunction "DB11_17") (pintype "passive"))
      (node (ref "LCD-MODULE") (pin "6") (pinfunction "DB11_6") (pintype "passive"))
    )
    (net (code "43") (name "Net-(J7-DB12)") (class "Default")
      (node (ref "J7") (pin "18") (pinfunction "DB12_18") (pintype "passive"))
      (node (ref "LCD-MODULE") (pin "7") (pinfunction "DB12_7") (pintype "passive"))
    )
    (net (code "44") (name "Net-(J7-DB13)") (class "Default")
      (node (ref "J7") (pin "19") (pinfunction "DB13_19") (pintype "passive"))
      (node (ref "LCD-MODULE") (pin "8") (pinfunction "DB13_8") (pintype "passive"))
    )
    (net (code "45") (name "Net-(J7-DB14)") (class "Default")
      (node (ref "J7") (pin "20") (pinfunction "DB14_20") (pintype "passive"))
      (node (ref "LCD-MODULE") (pin "9") (pinfunction "DB14_9") (pintype "passive"))
    )
    (net (code "46") (name "Net-(J7-DB15)") (class "Default")
      (node (ref "J7") (pin "21") (pinfunction "DB15_21") (pintype "passive"))
      (node (ref "LCD-MODULE") (pin "10") (pinfunction "DB15_10") (pintype "passive"))
    )
    (net (code "47") (name "Net-(J7-RD)") (class "Default")
      (node (ref "J7") (pin "4") (pinfunction "RD_4") (pintype "passive"))
      (node (ref "LCD-MODULE") (pin "26") (pinfunction "LCD_RD_26") (pintype "passive"))
    )
    (net (code "48") (name "Net-(J7-RS)") (class "Default")
      (node (ref "J7") (pin "2") (pinfunction "RS_2") (pintype "passive"))
      (node (ref "LCD-MODULE") (pin "19") (pinfunction "LCD_RS_19") (pintype "passive"))
    )
    (net (code "49") (name "Net-(J7-RST)") (class "Default")
      (node (ref "J7") (pin "5") (pinfunction "RST_5") (pintype "passive"))
      (node (ref "LCD-MODULE") (pin "22") (pinfunction "LCD_RST_22") (pintype "passive"))
    )
    (net (code "50") (name "Net-(J7-WR)") (class "Default")
      (node (ref "J7") (pin "3") (pinfunction "WR_3") (pintype "passive"))
      (node (ref "LCD-MODULE") (pin "20") (pinfunction "LCD_WR_20") (pintype "passive"))
    )
    (net (code "51") (name "Net-(R1-W)") (class "Default")
      (node (ref "R1") (pin "2") (pinfunction "W_2") (pintype "passive"))
      (node (ref "U2") (pin "7") (pinfunction "CH6_7") (pintype "passive"))
    )
    (net (code "52") (name "Net-(R2-W)") (class "Default")
      (node (ref "R2") (pin "2") (pinfunction "W_2") (pintype "passive"))
      (node (ref "U2") (pin "8") (pinfunction "CH7_8") (pintype "passive"))
    )
    (net (code "53") (name "Net-(S24-A-Pad1)") (class "Default")
      (node (ref "S24") (pin "1") (pinfunction "A_1") (pintype "passive"))
      (node (ref "S24") (pin "2") (pinfunction "A_2") (pintype "passive"))
    )
    (net (code "54") (name "Net-(S24-B-Pad3)") (class "Default")
      (node (ref "S24") (pin "3") (pinfunction "B_3") (pintype "passive"))
      (node (ref "S24") (pin "4") (pinfunction "B_4") (pintype "passive"))
    )
    (net (code "55") (name "Net-(S25-A-Pad1)") (class "Default")
      (node (ref "S25") (pin "1") (pinfunction "A_1") (pintype "passive"))
      (node (ref "S25") (pin "2") (pinfunction "A_2") (pintype "passive"))
    )
    (net (code "56") (name "Net-(S25-B-Pad3)") (class "Default")
      (node (ref "S25") (pin "3") (pinfunction "B_3") (pintype "passive"))
      (node (ref "S25") (pin "4") (pinfunction "B_4") (pintype "passive"))
    )
    (net (code "57") (name "Net-(S26-A-Pad1)") (class "Default")
      (node (ref "S26") (pin "1") (pinfunction "A_1") (pintype "passive"))
      (node (ref "S26") (pin "2") (pinfunction "A_2") (pintype "passive"))
    )
    (net (code "58") (name "Net-(S26-B-Pad3)") (class "Default")
      (node (ref "S26") (pin "3") (pinfunction "B_3") (pintype "passive"))
      (node (ref "S26") (pin "4") (pinfunction "B_4") (pintype "passive"))
    )
    (net (code "59") (name "Net-(S27-A-Pad1)") (class "Default")
      (node (ref "S27") (pin "1") (pinfunction "A_1") (pintype "passive"))
      (node (ref "S27") (pin "2") (pinfunction "A_2") (pintype "passive"))
    )
    (net (code "60") (name "Net-(S27-B-Pad3)") (class "Default")
      (node (ref "S27") (pin "3") (pinfunction "B_3") (pintype "passive"))
      (node (ref "S27") (pin "4") (pinfunction "B_4") (pintype "passive"))
    )
    (net (code "61") (name "Net-(U1-CH0)") (class "Default")
      (node (ref "R9") (pin "1") (pinfunction "1_1") (pintype "passive"))
      (node (ref "S8") (pin "1") (pinfunction "A_1") (pintype "passive"))
      (node (ref "S8") (pin "2") (pinfunction "A_2") (pintype "passive"))
      (node (ref "U1") (pin "1") (pinfunction "CH0_1") (pintype "passive"))
    )
    (net (code "62") (name "Net-(U1-CH1)") (class "Default")
      (node (ref "R10") (pin "1") (pinfunction "1_1") (pintype "passive"))
      (node (ref "S7") (pin "1") (pinfunction "A_1") (pintype "passive"))
      (node (ref "S7") (pin "2") (pinfunction "A_2") (pintype "passive"))
      (node (ref "U1") (pin "2") (pinfunction "CH1_2") (pintype "passive"))
    )
    (net (code "63") (name "Net-(U1-CH2)") (class "Default")
      (node (ref "R8") (pin "1") (pinfunction "1_1") (pintype "passive"))
      (node (ref "S6") (pin "1") (pinfunction "A_1") (pintype "passive"))
      (node (ref "S6") (pin "2") (pinfunction "A_2") (pintype "passive"))
      (node (ref "U1") (pin "3") (pinfunction "CH2_3") (pintype "passive"))
    )
    (net (code "64") (name "Net-(U1-CH3)") (class "Default")
      (node (ref "R7") (pin "1") (pinfunction "1_1") (pintype "passive"))
      (node (ref "S5") (pin "1") (pinfunction "A_1") (pintype "passive"))
      (node (ref "S5") (pin "2") (pinfunction "A_2") (pintype "passive"))
      (node (ref "U1") (pin "4") (pinfunction "CH3_4") (pintype "passive"))
    )
    (net (code "65") (name "Net-(U1-CH4)") (class "Default")
      (node (ref "R6") (pin "1") (pinfunction "1_1") (pintype "passive"))
      (node (ref "S4") (pin "1") (pinfunction "A_1") (pintype "passive"))
      (node (ref "S4") (pin "2") (pinfunction "A_2") (pintype "passive"))
      (node (ref "U1") (pin "5") (pinfunction "CH4_5") (pintype "passive"))
    )
    (net (code "66") (name "Net-(U1-CH5)") (class "Default")
      (node (ref "R5") (pin "1") (pinfunction "1_1") (pintype "passive"))
      (node (ref "S3") (pin "1") (pinfunction "A_1") (pintype "passive"))
      (node (ref "S3") (pin "2") (pinfunction "A_2") (pintype "passive"))
      (node (ref "U1") (pin "6") (pinfunction "CH5_6") (pintype "passive"))
    )
    (net (code "67") (name "Net-(U1-CH6)") (class "Default")
      (node (ref "R4") (pin "1") (pinfunction "1_1") (pintype "passive"))
      (node (ref "S2") (pin "1") (pinfunction "A_1") (pintype "passive"))
      (node (ref "S2") (pin "2") (pinfunction "A_2") (pintype "passive"))
      (node (ref "U1") (pin "7") (pinfunction "CH6_7") (pintype "passive"))
    )
    (net (code "68") (name "Net-(U1-CH7)") (class "Default")
      (node (ref "R3") (pin "1") (pinfunction "1_1") (pintype "passive"))
      (node (ref "S1") (pin "1") (pinfunction "A_1") (pintype "passive"))
      (node (ref "S1") (pin "2") (pinfunction "A_2") (pintype "passive"))
      (node (ref "U1") (pin "8") (pinfunction "CH7_8") (pintype "passive"))
    )
    (net (code "69") (name "Net-(U2-CH0)") (class "Default")
      (node (ref "R16") (pin "1") (pinfunction "1_1") (pintype "passive"))
      (node (ref "S14") (pin "1") (pinfunction "A_1") (pintype "passive"))
      (node (ref "S14") (pin "2") (pinfunction "A_2") (pintype "passive"))
      (node (ref "U2") (pin "1") (pinfunction "CH0_1") (pintype "passive"))
    )
    (net (code "70") (name "Net-(U2-CH1)") (class "Default")
      (node (ref "R15") (pin "1") (pinfunction "1_1") (pintype "passive"))
      (node (ref "S13") (pin "1") (pinfunction "A_1") (pintype "passive"))
      (node (ref "S13") (pin "2") (pinfunction "A_2") (pintype "passive"))
      (node (ref "U2") (pin "2") (pinfunction "CH1_2") (pintype "passive"))
    )
    (net (code "71") (name "Net-(U2-CH2)") (class "Default")
      (node (ref "R14") (pin "1") (pinfunction "1_1") (pintype "passive"))
      (node (ref "S12") (pin "1") (pinfunction "A_1") (pintype "passive"))
      (node (ref "S12") (pin "2") (pinfunction "A_2") (pintype "passive"))
      (node (ref "U2") (pin "3") (pinfunction "CH2_3") (pintype "passive"))
    )
    (net (code "72") (name "Net-(U2-CH3)") (class "Default")
      (node (ref "R13") (pin "1") (pinfunction "1_1") (pintype "passive"))
      (node (ref "S11") (pin "1") (pinfunction "A_1") (pintype "passive"))
      (node (ref "S11") (pin "2") (pinfunction "A_2") (pintype "passive"))
      (node (ref "U2") (pin "4") (pinfunction "CH3_4") (pintype "passive"))
    )
    (net (code "73") (name "Net-(U2-CH4)") (class "Default")
      (node (ref "R12") (pin "1") (pinfunction "1_1") (pintype "passive"))
      (node (ref "S10") (pin "1") (pinfunction "A_1") (pintype "passive"))
      (node (ref "S10") (pin "2") (pinfunction "A_2") (pintype "passive"))
      (node (ref "U2") (pin "5") (pinfunction "CH4_5") (pintype "passive"))
    )
    (net (code "74") (name "Net-(U2-CH5)") (class "Default")
      (node (ref "R11") (pin "1") (pinfunction "1_1") (pintype "passive"))
      (node (ref "S9") (pin "1") (pinfunction "A_1") (pintype "passive"))
      (node (ref "S9") (pin "2") (pinfunction "A_2") (pintype "passive"))
      (node (ref "U2") (pin "6") (pinfunction "CH5_6") (pintype "passive"))
    )
    (net (code "75") (name "Net-(U3-CH0)") (class "Default")
      (node (ref "R29") (pin "1") (pinfunction "1_1") (pintype "passive"))
      (node (ref "S23") (pin "1") (pinfunction "A_1") (pintype "passive"))
      (node (ref "S23") (pin "2") (pinfunction "A_2") (pintype "passive"))
      (node (ref "U3") (pin "1") (pinfunction "CH0_1") (pintype "passive"))
    )
    (net (code "76") (name "Net-(U3-CH1)") (class "Default")
      (node (ref "R30") (pin "1") (pinfunction "1_1") (pintype "passive"))
      (node (ref "S22") (pin "1") (pinfunction "A_1") (pintype "passive"))
      (node (ref "S22") (pin "2") (pinfunction "A_2") (pintype "passive"))
      (node (ref "U3") (pin "2") (pinfunction "CH1_2") (pintype "passive"))
    )
    (net (code "77") (name "Net-(U3-CH2)") (class "Default")
      (node (ref "R31") (pin "1") (pinfunction "1_1") (pintype "passive"))
      (node (ref "S21") (pin "1") (pinfunction "A_1") (pintype "passive"))
      (node (ref "S21") (pin "2") (pinfunction "A_2") (pintype "passive"))
      (node (ref "U3") (pin "3") (pinfunction "CH2_3") (pintype "passive"))
    )
    (net (code "78") (name "Net-(U3-CH3)") (class "Default")
      (node (ref "R32") (pin "1") (pinfunction "1_1") (pintype "passive"))
      (node (ref "S20") (pin "1") (pinfunction "A_1") (pintype "passive"))
      (node (ref "S20") (pin "2") (pinfunction "A_2") (pintype "passive"))
      (node (ref "U3") (pin "4") (pinfunction "CH3_4") (pintype "passive"))
    )
    (net (code "79") (name "Net-(U3-CH4)") (class "Default")
      (node (ref "R33") (pin "1") (pinfunction "1_1") (pintype "passive"))
      (node (ref "S19") (pin "1") (pinfunction "A_1") (pintype "passive"))
      (node (ref "S19") (pin "2") (pinfunction "A_2") (pintype "passive"))
      (node (ref "U3") (pin "5") (pinfunction "CH4_5") (pintype "passive"))
    )
    (net (code "80") (name "Net-(U3-CH5)") (class "Default")
      (node (ref "R34") (pin "1") (pinfunction "1_1") (pintype "passive"))
      (node (ref "S18") (pin "1") (pinfunction "A_1") (pintype "passive"))
      (node (ref "S18") (pin "2") (pinfunction "A_2") (pintype "passive"))
      (node (ref "U3") (pin "6") (pinfunction "CH5_6") (pintype "passive"))
    )
    (net (code "81") (name "Net-(U3-CH6)") (class "Default")
      (node (ref "R35") (pin "1") (pinfunction "1_1") (pintype "passive"))
      (node (ref "S17") (pin "1") (pinfunction "A_1") (pintype "passive"))
      (node (ref "S17") (pin "2") (pinfunction "A_2") (pintype "passive"))
      (node (ref "U3") (pin "7") (pinfunction "CH6_7") (pintype "passive"))
    )
    (net (code "82") (name "Net-(U3-CH7)") (class "Default")
      (node (ref "R36") (pin "1") (pinfunction "1_1") (pintype "passive"))
      (node (ref "S16") (pin "1") (pinfunction "A_1") (pintype "passive"))
      (node (ref "S16") (pin "2") (pinfunction "A_2") (pintype "passive"))
      (node (ref "U3") (pin "8") (pinfunction "CH7_8") (pintype "passive"))
    )
    (net (code "83") (name "VCC12_IN") (class "Default")
      (node (ref "ACCUM") (pin "2") (pinfunction "2_2") (pintype "passive"))
      (node (ref "Q1") (pin "3") (pinfunction "S_3") (pintype "passive"))
      (node (ref "R26") (pin "2") (pinfunction "2_2") (pintype "passive"))
      (node (ref "R27") (pin "2") (pinfunction "2_2") (pintype "passive"))
      (node (ref "T1") (pin "LCP") (pinfunction "P2_LCP") (pintype "passive"))
    )
    (net (code "84") (name "unconnected-(ESP-8266-GPIO0-Pad3)") (class "Default")
      (node (ref "ESP-8266") (pin "3") (pinfunction "GPIO0_3") (pintype "passive"))
    )
    (net (code "85") (name "unconnected-(ESP-8266-GPIO2-Pad2)") (class "Default")
      (node (ref "ESP-8266") (pin "2") (pinfunction "GPIO2_2") (pintype "passive"))
    )
    (net (code "86") (name "unconnected-(ESP-8266-GPIO16-Pad7)") (class "Default")
      (node (ref "ESP-8266") (pin "7") (pinfunction "GPIO16_7") (pintype "passive"))
    )
    (net (code "87") (name "unconnected-(J2-DAT1-Pad8)") (class "Default")
      (node (ref "J2") (pin "8") (pinfunction "DAT1_8") (pintype "passive"))
    )
    (net (code "88") (name "unconnected-(J2-DAT2-Pad1)") (class "Default")
      (node (ref "J2") (pin "1") (pinfunction "DAT2_1") (pintype "passive"))
    )
    (net (code "89") (name "unconnected-(J2-PadMP3)") (class "Default")
      (node (ref "J2") (pin "MP3") (pinfunction "MP3_MP3") (pintype "passive"))
    )
    (net (code "90") (name "unconnected-(LCD-MODULE-NC-Pad23)") (class "Default")
      (node (ref "LCD-MODULE") (pin "23") (pinfunction "NC_23") (pintype "passive"))
    )
    (net (code "91") (name "unconnected-(LCD-MODULE-NC-Pad24)") (class "Default")
      (node (ref "LCD-MODULE") (pin "24") (pinfunction "NC_24") (pintype "passive"))
    )
    (net (code "92") (name "unconnected-(LCD-MODULE-NC-Pad25)") (class "Default")
      (node (ref "LCD-MODULE") (pin "25") (pinfunction "NC_25") (pintype "passive"))
    )
    (net (code "93") (name "unconnected-(LCD-MODULE-NC-Pad27)") (class "Default")
      (node (ref "LCD-MODULE") (pin "27") (pinfunction "NC_27") (pintype "passive"))
    )
    (net (code "94") (name "unconnected-(LCD-MODULE-NC-Pad28)") (class "Default")
      (node (ref "LCD-MODULE") (pin "28") (pinfunction "NC_28") (pintype "passive"))
    )
    (net (code "95") (name "unconnected-(LCD-MODULE-NC-Pad29)") (class "Default")
      (node (ref "LCD-MODULE") (pin "29") (pinfunction "NC_29") (pintype "passive"))
    )
    (net (code "96") (name "unconnected-(LCD-MODULE-NC-Pad30)") (class "Default")
      (node (ref "LCD-MODULE") (pin "30") (pinfunction "NC_30") (pintype "passive"))
    )
    (net (code "97") (name "unconnected-(LCD-MODULE-RESET-Pad37)") (class "Default")
      (node (ref "LCD-MODULE") (pin "37") (pinfunction "RESET_37") (pintype "passive"))
    )
    (net (code "98") (name "unconnected-(LCD-MODULE-SD_CLK-Pad33)") (class "Default")
      (node (ref "LCD-MODULE") (pin "33") (pinfunction "SD_CLK_33") (pintype "passive"))
    )
    (net (code "99") (name "unconnected-(LCD-MODULE-SD_CS-Pad34)") (class "Default")
      (node (ref "LCD-MODULE") (pin "34") (pinfunction "SD_CS_34") (pintype "passive"))
    )
    (net (code "100") (name "unconnected-(LCD-MODULE-SD_MISO-Pad31)") (class "Default")
      (node (ref "LCD-MODULE") (pin "31") (pinfunction "SD_MISO_31") (pintype "passive"))
    )
    (net (code "101") (name "unconnected-(LCD-MODULE-SD_MOSI-Pad32)") (class "Default")
      (node (ref "LCD-MODULE") (pin "32") (pinfunction "SD_MOSI_32") (pintype "passive"))
    )
  )
)
